# LED_1.net
KiCad netlist of a schematic drawn in Altium Designer
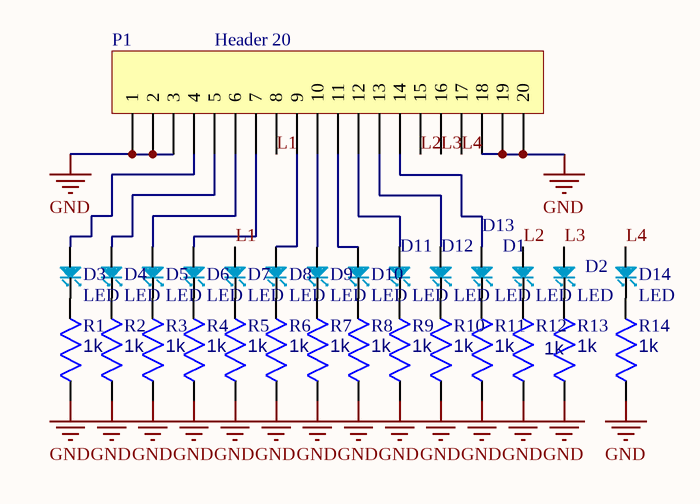
[diagram p0: LED_1.SchDoc]

(export (version "E")
  (design (tool "Eeschema 10.0.6"))
  (components
    (comp (ref "D1") (value "LED") (footprint "1206") (libsource (lib "My_lib") (part "LED")))
    (comp (ref "D2") (value "LED") (footprint "1206") (libsource (lib "My_lib") (part "LED")))
    (comp (ref "D3") (value "LED") (footprint "1206") (libsource (lib "My_lib") (part "LED")))
    (comp (ref "D4") (value "LED") (footprint "1206") (libsource (lib "My_lib") (part "LED")))
    (comp (ref "D5") (value "LED") (footprint "1206") (libsource (lib "My_lib") (part "LED")))
    (comp (ref "D6") (value "LED") (footprint "1206") (libsource (lib "My_lib") (part "LED")))
    (comp (ref "D7") (value "LED") (footprint "1206") (libsource (lib "My_lib") (part "LED")))
    (comp (ref "D8") (value "LED") (footprint "1206") (libsource (lib "My_lib") (part "LED")))
    (comp (ref "D9") (value "LED") (footprint "1206") (libsource (lib "My_lib") (part "LED")))
    (comp (ref "D10") (value "LED") (footprint "1206") (libsource (lib "My_lib") (part "LED")))
    (comp (ref "D11") (value "LED") (footprint "1206") (libsource (lib "My_lib") (part "LED")))
    (comp (ref "D12") (value "LED") (footprint "1206") (libsource (lib "My_lib") (part "LED")))
    (comp (ref "D13") (value "LED") (footprint "1206") (libsource (lib "My_lib") (part "LED")))
    (comp (ref "D14") (value "LED") (footprint "1206") (libsource (lib "My_lib") (part "LED")))
    (comp (ref "P1")
      (value "Header 20")
      (footprint "HDR1X20")
      (description "Header, 20-Pin")
      (fields (field (name "PUBLISHER") "Altium Limited"))
      (libsource (lib "Miscellaneous Connectors") (part "Header 20"))
    )
    (comp (ref "R1")
      (value "1k")
      (footprint "R_0805")
      (description "Resistor")
      (libsource (lib "My_LIB") (part "Res 0805"))
    )
    (comp (ref "R2")
      (value "1k")
      (footprint "R_0805")
      (description "Resistor")
      (libsource (lib "My_LIB") (part "Res 0805"))
    )
    (comp (ref "R3")
      (value "1k")
      (footprint "R_0805")
      (description "Resistor")
      (libsource (lib "My_LIB") (part "Res 0805"))
    )
    (comp (ref "R4")
      (value "1k")
      (footprint "R_0805")
      (description "Resistor")
      (libsource (lib "My_LIB") (part "Res 0805"))
    )
    (comp (ref "R5")
      (value "1k")
      (footprint "R_0805")
      (description "Resistor")
      (libsource (lib "My_LIB") (part "Res 0805"))
    )
    (comp (ref "R6")
      (value "1k")
      (footprint "R_0805")
      (description "Resistor")
      (libsource (lib "My_LIB") (part "Res 0805"))
    )
    (comp (ref "R7")
      (value "1k")
      (footprint "R_0805")
      (description "Resistor")
      (libsource (lib "My_LIB") (part "Res 0805"))
    )
    (comp (ref "R8")
      (value "1k")
      (footprint "R_0805")
      (description "Resistor")
      (libsource (lib "My_LIB") (part "Res 0805"))
    )
    (comp (ref "R9")
      (value "1k")
      (footprint "R_0805")
      (description "Resistor")
      (libsource (lib "My_LIB") (part "Res 0805"))
    )
    (comp (ref "R10")
      (value "1k")
      (footprint "R_0805")
      (description "Resistor")
      (libsource (lib "My_LIB") (part "Res 0805"))
    )
    (comp (ref "R11")
      (value "1k")
      (footprint "R_0805")
      (description "Resistor")
      (libsource (lib "My_LIB") (part "Res 0805"))
    )
    (comp (ref "R12")
      (value "1k")
      (footprint "R_0805")
      (description "Resistor")
      (libsource (lib "My_LIB") (part "Res 0805"))
    )
    (comp (ref "R13")
      (value "1k")
      (footprint "R_0805")
      (description "Resistor")
      (libsource (lib "My_LIB") (part "Res 0805"))
    )
    (comp (ref "R14")
      (value "1k")
      (footprint "R_0805")
      (description "Resistor")
      (libsource (lib "My_LIB") (part "Res 0805"))
    )
  )
  (nets
    (net (code "1") (name "/L1") (class "Default")
      (node (ref "D7") (pin "1") (pintype "passive"))
      (node (ref "P1") (pin "8") (pinfunction "8_8") (pintype "passive"))
    )
    (net (code "2") (name "/L2") (class "Default")
      (node (ref "D1") (pin "1") (pintype "passive"))
      (node (ref "P1") (pin "15") (pinfunction "15_15") (pintype "passive"))
    )
    (net (code "3") (name "/L3") (class "Default")
      (node (ref "D2") (pin "1") (pintype "passive"))
      (node (ref "P1") (pin "16") (pinfunction "16_16") (pintype "passive"))
    )
    (net (code "4") (name "/L4") (class "Default")
      (node (ref "D14") (pin "1") (pintype "passive"))
      (node (ref "P1") (pin "17") (pinfunction "17_17") (pintype "passive"))
    )
    (net (code "5") (name "GND") (class "Default")
      (node (ref "P1") (pin "1") (pinfunction "1_1") (pintype "passive"))
      (node (ref "P1") (pin "18") (pinfunction "18_18") (pintype "passive"))
      (node (ref "P1") (pin "19") (pinfunction "19_19") (pintype "passive"))
      (node (ref "P1") (pin "2") (pinfunction "2_2") (pintype "passive"))
      (node (ref "P1") (pin "20") (pinfunction "20_20") (pintype "passive"))
      (node (ref "P1") (pin "3") (pinfunction "3_3") (pintype "passive"))
      (node (ref "R1") (pin "2") (pintype "passive"))
      (node (ref "R10") (pin "2") (pintype "passive"))
      (node (ref "R11") (pin "2") (pintype "passive"))
      (node (ref "R12") (pin "2") (pintype "passive"))
      (node (ref "R13") (pin "2") (pintype "passive"))
      (node (ref "R14") (pin "2") (pintype "passive"))
      (node (ref "R2") (pin "2") (pintype "passive"))
      (node (ref "R3") (pin "2") (pintype "passive"))
      (node (ref "R4") (pin "2") (pintype "passive"))
      (node (ref "R5") (pin "2") (pintype "passive"))
      (node (ref "R6") (pin "2") (pintype "passive"))
      (node (ref "R7") (pin "2") (pintype "passive"))
      (node (ref "R8") (pin "2") (pintype "passive"))
      (node (ref "R9") (pin "2") (pintype "passive"))
    )
    (net (code "6") (name "Net-(D1-Pad2)") (class "Default")
      (node (ref "D1") (pin "2") (pintype "passive"))
      (node (ref "R12") (pin "1") (pintype "passive"))
    )
    (net (code "7") (name "Net-(D2-Pad2)") (class "Default")
      (node (ref "D2") (pin "2") (pintype "passive"))
      (node (ref "R13") (pin "1") (pintype "passive"))
    )
    (net (code "8") (name "Net-(D3-Pad1)") (class "Default")
      (node (ref "D3") (pin "1") (pintype "passive"))
      (node (ref "P1") (pin "4") (pinfunction "4_4") (pintype "passive"))
    )
    (net (code "9") (name "Net-(D3-Pad2)") (class "Default")
      (node (ref "D3") (pin "2") (pintype "passive"))
      (node (ref "R1") (pin "1") (pintype "passive"))
    )
    (net (code "10") (name "Net-(D4-Pad1)") (class "Default")
      (node (ref "D4") (pin "1") (pintype "passive"))
      (node (ref "P1") (pin "5") (pinfunction "5_5") (pintype "passive"))
    )
    (net (code "11") (name "Net-(D4-Pad2)") (class "Default")
      (node (ref "D4") (pin "2") (pintype "passive"))
      (node (ref "R2") (pin "1") (pintype "passive"))
    )
    (net (code "12") (name "Net-(D5-Pad1)") (class "Default")
      (node (ref "D5") (pin "1") (pintype "passive"))
      (node (ref "P1") (pin "6") (pinfunction "6_6") (pintype "passive"))
    )
    (net (code "13") (name "Net-(D5-Pad2)") (class "Default")
      (node (ref "D5") (pin "2") (pintype "passive"))
      (node (ref "R3") (pin "1") (pintype "passive"))
    )
    (net (code "14") (name "Net-(D6-Pad1)") (class "Default")
      (node (ref "D6") (pin "1") (pintype "passive"))
      (node (ref "P1") (pin "7") (pinfunction "7_7") (pintype "passive"))
    )
    (net (code "15") (name "Net-(D6-Pad2)") (class "Default")
      (node (ref "D6") (pin "2") (pintype "passive"))
      (node (ref "R4") (pin "1") (pintype "passive"))
    )
    (net (code "16") (name "Net-(D7-Pad2)") (class "Default")
      (node (ref "D7") (pin "2") (pintype "passive"))
      (node (ref "R5") (pin "1") (pintype "passive"))
    )
    (net (code "17") (name "Net-(D8-Pad1)") (class "Default")
      (node (ref "D8") (pin "1") (pintype "passive"))
      (node (ref "P1") (pin "9") (pinfunction "9_9") (pintype "passive"))
    )
    (net (code "18") (name "Net-(D8-Pad2)") (class "Default")
      (node (ref "D8") (pin "2") (pintype "passive"))
      (node (ref "R6") (pin "1") (pintype "passive"))
    )
    (net (code "19") (name "Net-(D9-Pad1)") (class "Default")
      (node (ref "D9") (pin "1") (pintype "passive"))
      (node (ref "P1") (pin "10") (pinfunction "10_10") (pintype "passive"))
    )
    (net (code "20") (name "Net-(D9-Pad2)") (class "Default")
      (node (ref "D9") (pin "2") (pintype "passive"))
      (node (ref "R7") (pin "1") (pintype "passive"))
    )
    (net (code "21") (name "Net-(D10-Pad1)") (class "Default")
      (node (ref "D10") (pin "1") (pintype "passive"))
      (node (ref "P1") (pin "11") (pinfunction "11_11") (pintype "passive"))
    )
    (net (code "22") (name "Net-(D10-Pad2)") (class "Default")
      (node (ref "D10") (pin "2") (pintype "passive"))
      (node (ref "R8") (pin "1") (pintype "passive"))
    )
    (net (code "23") (name "Net-(D11-Pad1)") (class "Default")
      (node (ref "D11") (pin "1") (pintype "passive"))
      (node (ref "P1") (pin "12") (pinfunction "12_12") (pintype "passive"))
    )
    (net (code "24") (name "Net-(D11-Pad2)") (class "Default")
      (node (ref "D11") (pin "2") (pintype "passive"))
      (node (ref "R9") (pin "1") (pintype "passive"))
    )
    (net (code "25") (name "Net-(D12-Pad1)") (class "Default")
      (node (ref "D12") (pin "1") (pintype "passive"))
      (node (ref "P1") (pin "13") (pinfunction "13_13") (pintype "passive"))
    )
    (net (code "26") (name "Net-(D12-Pad2)") (class "Default")
      (node (ref "D12") (pin "2") (pintype "passive"))
      (node (ref "R10") (pin "1") (pintype "passive"))
    )
    (net (code "27") (name "Net-(D13-Pad1)") (class "Default")
      (node (ref "D13") (pin "1") (pintype "passive"))
      (node (ref "P1") (pin "14") (pinfunction "14_14") (pintype "passive"))
    )
    (net (code "28") (name "Net-(D13-Pad2)") (class "Default")
      (node (ref "D13") (pin "2") (pintype "passive"))
      (node (ref "R11") (pin "1") (pintype "passive"))
    )
    (net (code "29") (name "Net-(D14-Pad2)") (class "Default")
      (node (ref "D14") (pin "2") (pintype "passive"))
      (node (ref "R14") (pin "1") (pintype "passive"))
    )
  )
)
